# PEAK_LCW.net
KiCad netlist of a schematic drawn in Altium Designer
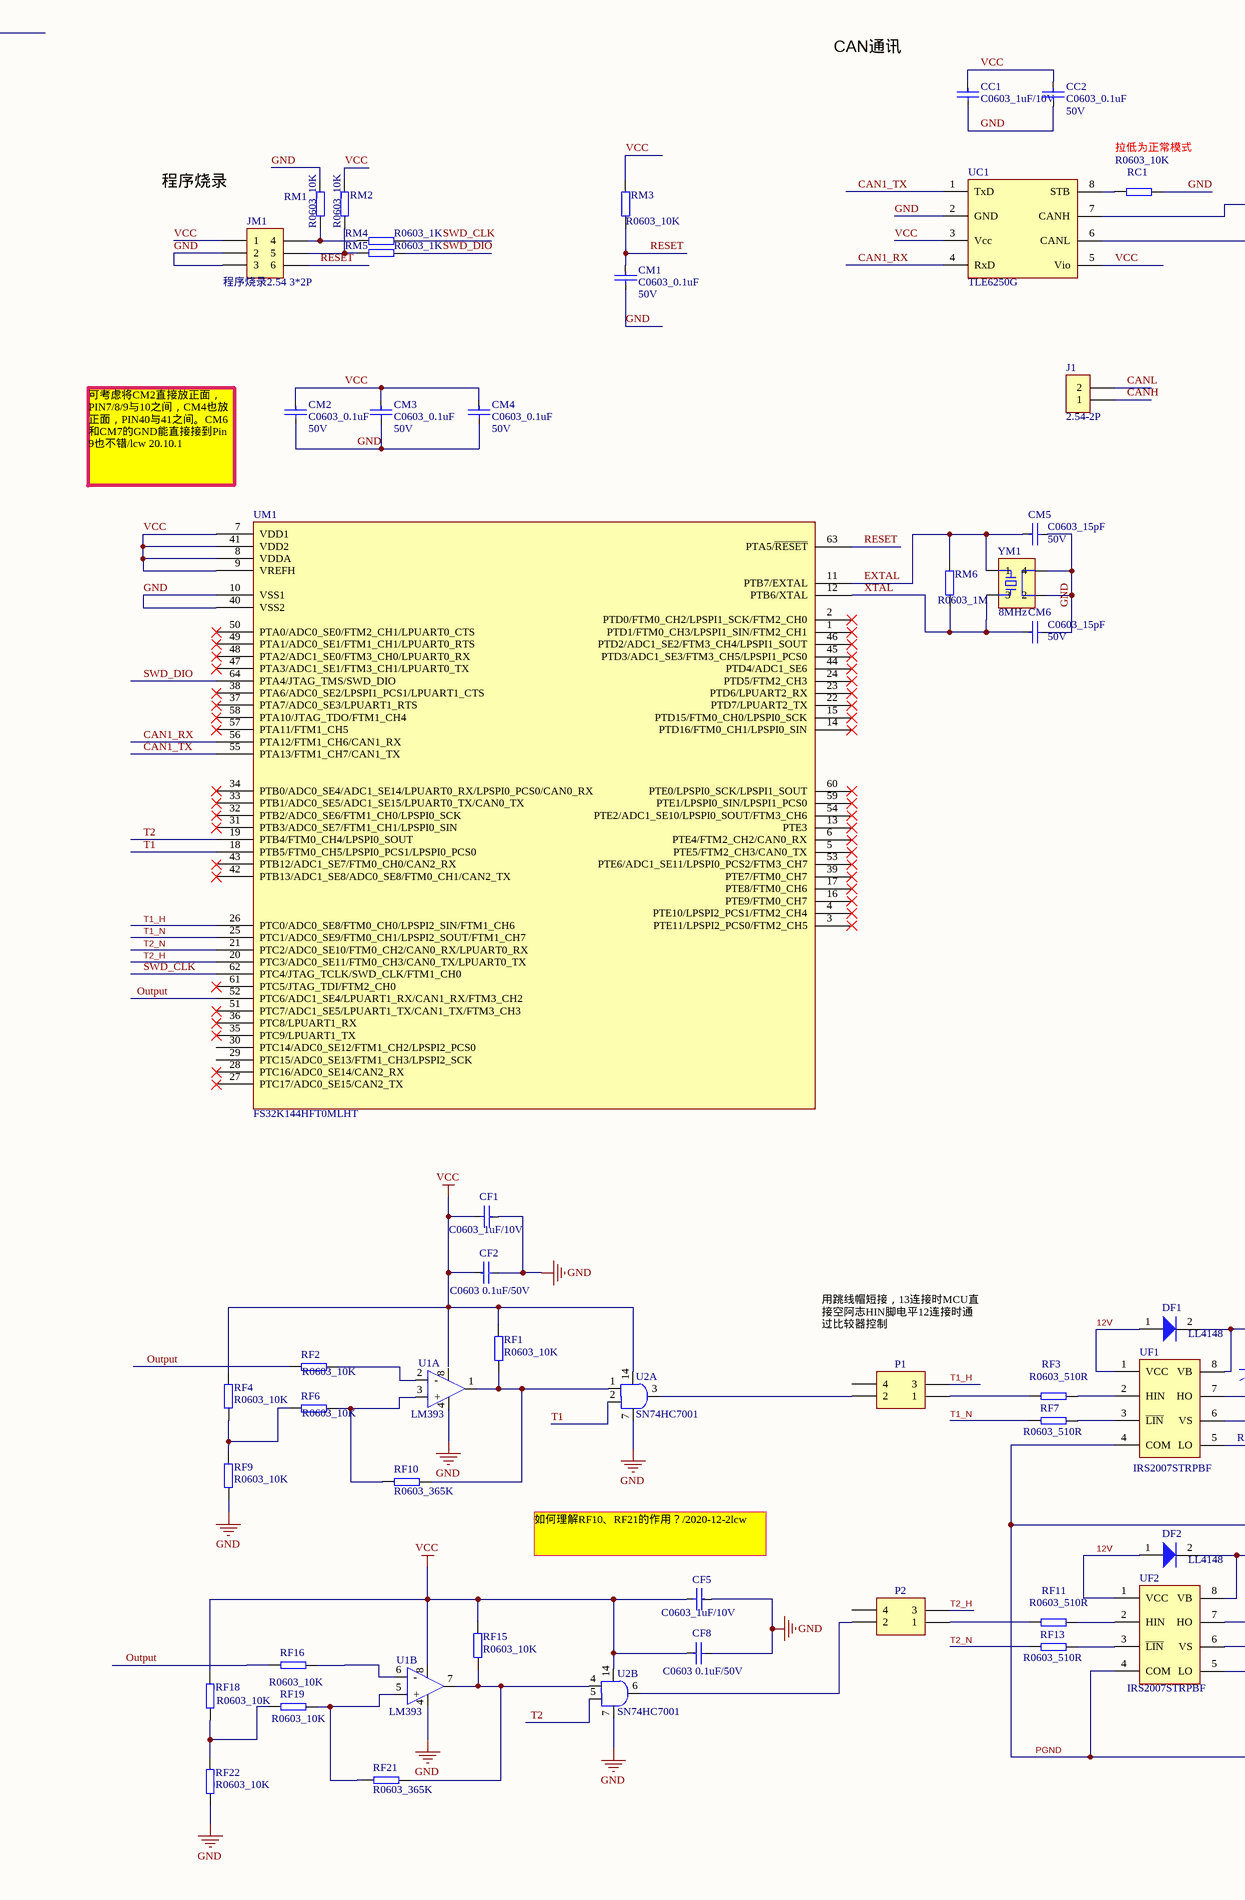
[diagram p0: PEAK——LCW.SchDoc, left]
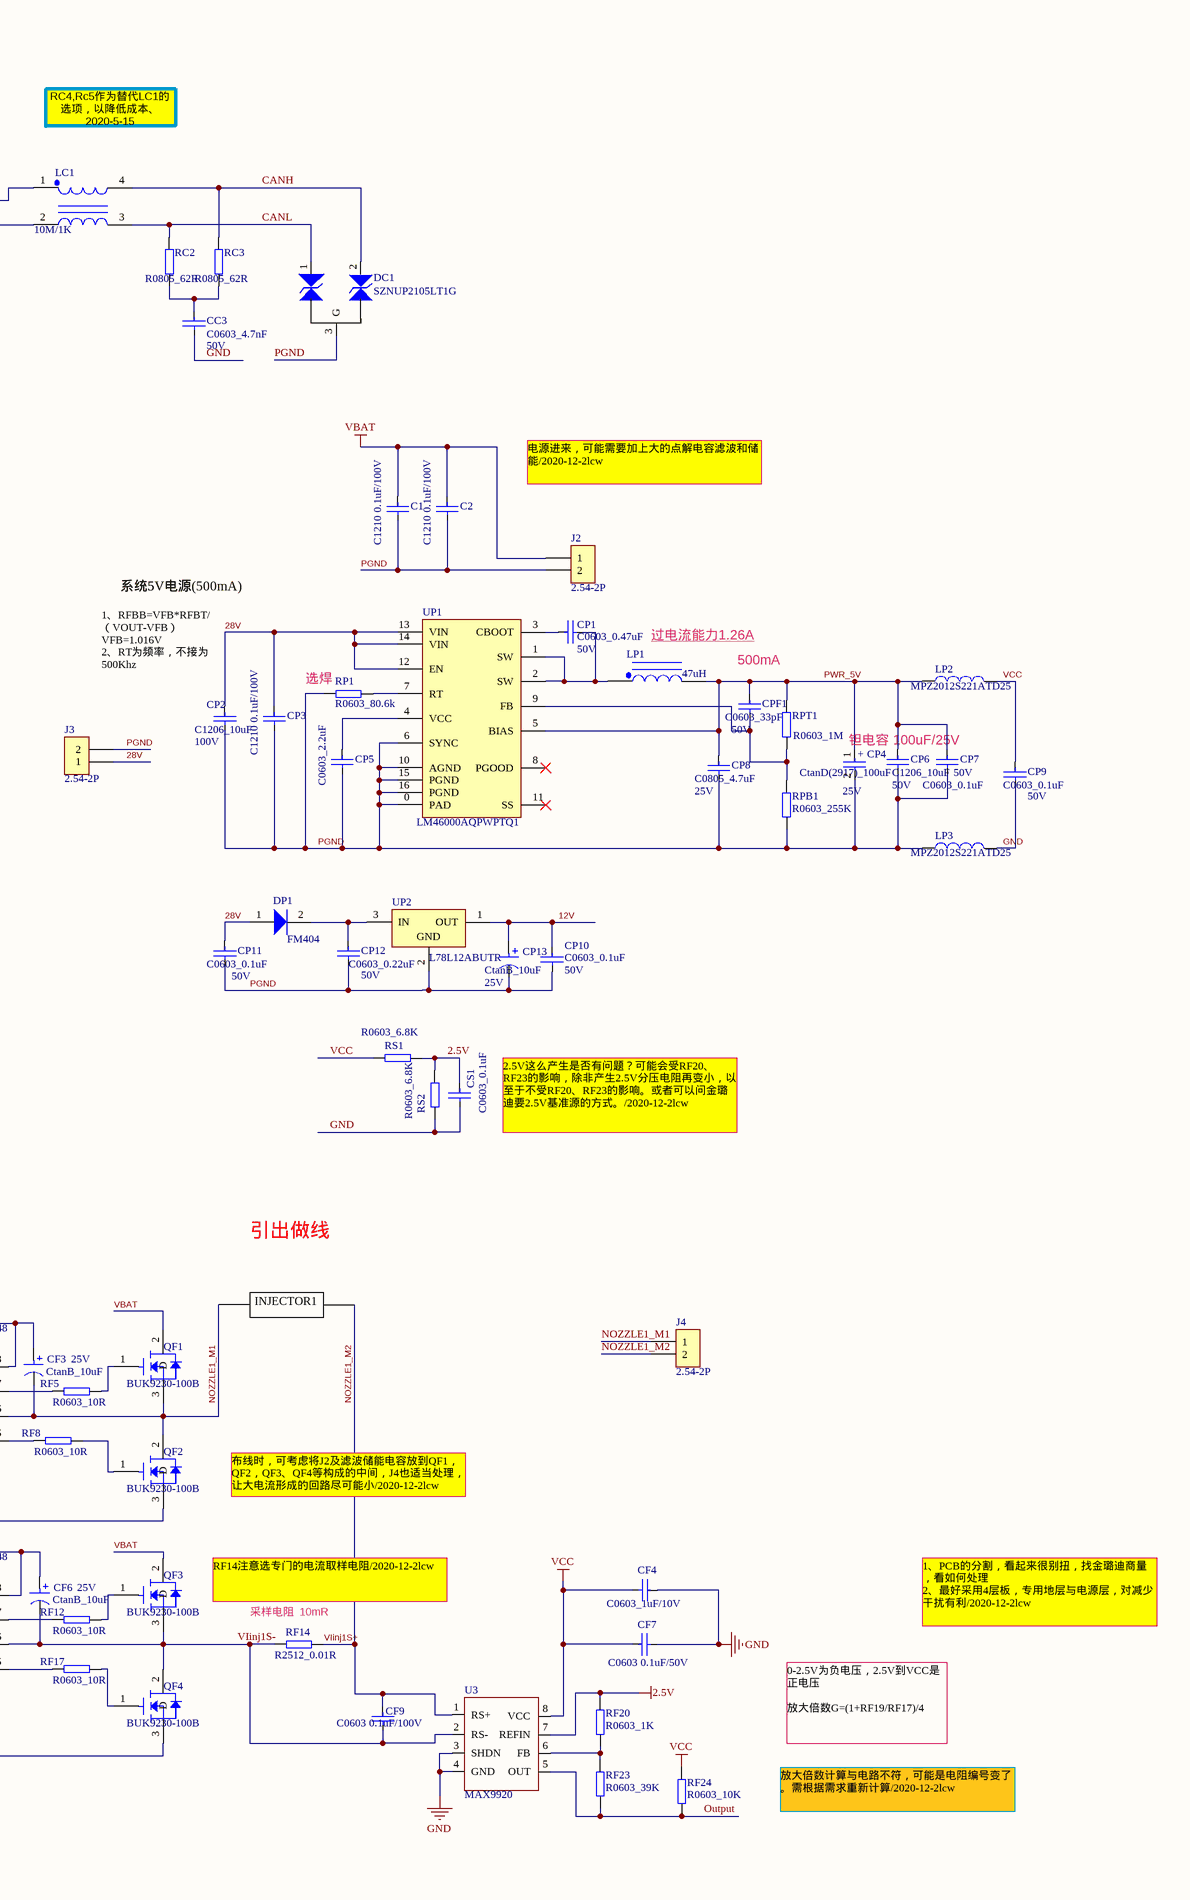
[diagram p1: PEAK——LCW.SchDoc, right]

(export (version "E")
  (design (tool "Eeschema 10.0.6"))
  (components
    (comp (ref "C1")
      (value "C1210 0.1uF/100V")
      (footprint "C1210")
      (description "C1210 0.1uF/50V 10%")
      (fields (field (name "VOLTAGE") "100V") (field (name "PART NUMBER") "3170014005"))
      (libsource (lib "BMSer") (part "CAP"))
    )
    (comp (ref "C2")
      (value "C1210 0.1uF/100V")
      (footprint "C1210")
      (description "C1210 0.1uF/50V 10%")
      (fields (field (name "VOLTAGE") "100V") (field (name "PART NUMBER") "3170014005"))
      (libsource (lib "BMSer") (part "CAP"))
    )
    (comp (ref "CC1")
      (value "C0603_1uF/10V")
      (footprint "C0603")
      (description "C0603 0.1uF/50V 10%")
      (fields (field (name "VOLTAGE") "10V") (field (name "PART NUMBER") "3170011015"))
      (libsource (lib "BMSer") (part "CAP"))
    )
    (comp (ref "CC2")
      (value "C0603_0.1uF")
      (footprint "C0603")
      (description "C0603 0.1uF/50V 10%")
      (fields
        (field (name "VOLTAGE") "50V")
        (field (name "PART NUMBER") "3170011015")
        (field (name "MANUFACTURER") "YAGEO")
      )
      (libsource (lib "BMSer") (part "CAP"))
    )
    (comp (ref "CC3")
      (value "C0603_4.7nF")
      (footprint "C0603")
      (description "C0603 4.7nF/50V 5% X7R")
      (fields
        (field (name "VOLTAGE") "50V")
        (field (name "PART NUMBER") "3170011009")
        (field (name "MANUFACTURER") "YAGEO")
      )
      (libsource (lib "BMSer") (part "CAP"))
    )
    (comp (ref "CF1")
      (value "C0603_1uF/10V")
      (footprint "C0603")
      (description "C0603 0.1uF/50V 10%")
      (fields (field (name "VOLTAGE") "10V") (field (name "PART NUMBER") "3170011015"))
      (libsource (lib "BMSer") (part "CAP"))
    )
    (comp (ref "CF2")
      (value "C0603 0.1uF/50V")
      (footprint "C0603")
      (description "C0603 0.1uF/50V 10%")
      (fields (field (name "VOLTAGE") "50V") (field (name "PART NUMBER") "3170011015"))
      (libsource (lib "BMSer") (part "CAP"))
    )
    (comp (ref "CF3")
      (value "CtanB_10uF")
      (footprint "CTANB")
      (description "CtanB(1210) 10uF/25V 10%")
      (fields
        (field (name "PART NUMBER") "3172690034")
        (field (name "MANUFACTURER") "AVX")
        (field (name "VOLTAGE") "25V")
      )
      (libsource (lib "BMSer") (part "CAP_T"))
    )
    (comp (ref "CF4")
      (value "C0603_1uF/10V")
      (footprint "C0603")
      (description "C0603 0.1uF/50V 10%")
      (fields (field (name "VOLTAGE") "10V") (field (name "PART NUMBER") "3170011015"))
      (libsource (lib "BMSer") (part "CAP"))
    )
    (comp (ref "CF5")
      (value "C0603_1uF/10V")
      (footprint "C0603")
      (description "C0603 0.1uF/50V 10%")
      (fields (field (name "VOLTAGE") "10V") (field (name "PART NUMBER") "3170011015"))
      (libsource (lib "BMSer") (part "CAP"))
    )
    (comp (ref "CF6")
      (value "CtanB_10uF")
      (footprint "CTANB")
      (description "CtanB(1210) 10uF/25V 10%")
      (fields
        (field (name "PART NUMBER") "3172690034")
        (field (name "MANUFACTURER") "AVX")
        (field (name "VOLTAGE") "25V")
      )
      (libsource (lib "BMSer") (part "CAP_T"))
    )
    (comp (ref "CF7")
      (value "C0603 0.1uF/50V")
      (footprint "C0603")
      (description "C0603 0.1uF/50V 10%")
      (fields (field (name "VOLTAGE") "50V") (field (name "PART NUMBER") "3170011015"))
      (libsource (lib "BMSer") (part "CAP"))
    )
    (comp (ref "CF8")
      (value "C0603 0.1uF/50V")
      (footprint "C0603")
      (description "C0603 0.1uF/50V 10%")
      (fields (field (name "VOLTAGE") "50V") (field (name "PART NUMBER") "3170011015"))
      (libsource (lib "BMSer") (part "CAP"))
    )
    (comp (ref "CF9")
      (value "C0603 0.1uF/100V")
      (footprint "C0603")
      (description "C0603 0.1uF/50V 10%")
      (fields (field (name "VOLTAGE") "50V") (field (name "PART NUMBER") "3170011015"))
      (libsource (lib "BMSer") (part "CAP"))
    )
    (comp (ref "CM1")
      (value "C0603_0.1uF")
      (footprint "C0603")
      (description "C0603 0.1uF/50V 10%")
      (fields
        (field (name "VOLTAGE") "50V")
        (field (name "PART NUMBER") "3170011015")
        (field (name "MANUFACTURER") "YAGEO")
      )
      (libsource (lib "BMSer") (part "CAP"))
    )
    (comp (ref "CM2")
      (value "C0603_0.1uF")
      (footprint "C0603")
      (description "C0603 0.1uF/50V 10%")
      (fields
        (field (name "VOLTAGE") "50V")
        (field (name "PART NUMBER") "3170011015")
        (field (name "MANUFACTURER") "YAGEO")
      )
      (libsource (lib "BMSer") (part "CAP"))
    )
    (comp (ref "CM3")
      (value "C0603_0.1uF")
      (footprint "C0603")
      (description "C0603 0.1uF/50V 10%")
      (fields
        (field (name "VOLTAGE") "50V")
        (field (name "PART NUMBER") "3170011015")
        (field (name "MANUFACTURER") "YAGEO")
      )
      (libsource (lib "BMSer") (part "CAP"))
    )
    (comp (ref "CM4")
      (value "C0603_0.1uF")
      (footprint "C0603")
      (description "C0603 0.1uF/50V 10%")
      (fields
        (field (name "VOLTAGE") "50V")
        (field (name "PART NUMBER") "3170011015")
        (field (name "MANUFACTURER") "YAGEO")
      )
      (libsource (lib "BMSer") (part "CAP"))
    )
    (comp (ref "CM5")
      (value "C0603_15pF")
      (footprint "C0603")
      (description "C0603 15pF/50V 10%")
      (fields
        (field (name "VOLTAGE") "50V")
        (field (name "PART NUMBER") "3172510040")
        (field (name "MANUFACTURER") "YAGEO")
      )
      (libsource (lib "BMSer") (part "CAP"))
    )
    (comp (ref "CM6")
      (value "C0603_15pF")
      (footprint "C0603")
      (description "C0603 15pF/50V 10%")
      (fields
        (field (name "VOLTAGE") "50V")
        (field (name "PART NUMBER") "3172510040")
        (field (name "MANUFACTURER") "YAGEO")
      )
      (libsource (lib "BMSer") (part "CAP"))
    )
    (comp (ref "CP1")
      (value "C0603_0.47uF")
      (footprint "C0603")
      (description "C0603 0.47uF/50V 10%")
      (fields
        (field (name "VOLTAGE") "50V")
        (field (name "PART NUMBER") "3170011017")
        (field (name "MANUFACTURER") "murata")
      )
      (libsource (lib "BMSer") (part "CAP"))
    )
    (comp (ref "CP2")
      (value "C1206_10uF")
      (footprint "C1206")
      (description "C1206 10uF/50V  10%")
      (fields
        (field (name "VOLTAGE") "100V")
        (field (name "PART NUMBER") "3172530019")
        (field (name "MANUFACTURER") "YAGEO")
      )
      (libsource (lib "BMSer") (part "CAP"))
    )
    (comp (ref "CP3")
      (value "C1210 0.1uF/100V")
      (footprint "C1210")
      (description "C1210 0.1uF/100V 10%")
      (fields (field (name "VOLTAGE") "100V") (field (name "PART NUMBER") "3170014005"))
      (libsource (lib "BMSer") (part "CAP"))
    )
    (comp (ref "CP4")
      (value "CtanD(2917)_100uF")
      (footprint "CTAND")
      (description "CtanD(2917) 100uF/25V 10%")
      (fields
        (field (name "VOLTAGE") "25V")
        (field (name "PART NUMBER") "3170030004")
        (field (name "MANUFACTURER") "AVX")
      )
      (libsource (lib "BMSer") (part "CAP_E"))
    )
    (comp (ref "CP5")
      (value "C0603_2.2uF")
      (footprint "C0603")
      (description "C0603 2.2uF/50V 10%")
      (fields (field (name "VOLTAGE") "50V") (field (name "PART NUMBER") "3170011030"))
      (libsource (lib "BMSer") (part "CAP"))
    )
    (comp (ref "CP6")
      (value "C1206_10uF")
      (footprint "C1206")
      (description "C1206 10uF/50V  10%")
      (fields
        (field (name "VOLTAGE") "50V")
        (field (name "PART NUMBER") "3172530019")
        (field (name "MANUFACTURER") "YAGEO")
      )
      (libsource (lib "BMSer") (part "CAP"))
    )
    (comp (ref "CP7")
      (value "C0603_0.1uF")
      (footprint "C0603")
      (description "C0603 0.1uF/50V 10%")
      (fields
        (field (name "VOLTAGE") "50V")
        (field (name "PART NUMBER") "3170011015")
        (field (name "MANUFACTURER") "YAGEO")
      )
      (libsource (lib "BMSer") (part "CAP"))
    )
    (comp (ref "CP8")
      (value "C0805_4.7uF")
      (footprint "C0805")
      (description "C0805 4.7uF/25V 10%")
      (fields
        (field (name "VOLTAGE") "25V")
        (field (name "PART NUMBER") "3170012010")
        (field (name "MANUFACTURER") "YAGEO")
      )
      (libsource (lib "BMSer") (part "CAP"))
    )
    (comp (ref "CP9")
      (value "C0603_0.1uF")
      (footprint "C0603")
      (description "C0603 0.1uF/50V 10%")
      (fields
        (field (name "VOLTAGE") "50V")
        (field (name "PART NUMBER") "3170011015")
        (field (name "MANUFACTURER") "YAGEO")
      )
      (libsource (lib "BMSer") (part "CAP"))
    )
    (comp (ref "CP10")
      (value "C0603_0.1uF")
      (footprint "C0603")
      (description "C0603 0.1uF/50V 10%  X7R")
      (fields
        (field (name "VOLTAGE") "50V")
        (field (name "PART NUMBER") "3170011015")
        (field (name "MANUFACTURER") "YAGEO")
      )
      (libsource (lib "BMSer") (part "CAP"))
    )
    (comp (ref "CP11")
      (value "C0603_0.1uF")
      (footprint "C0603")
      (description "C0603 0.1uF/50V 10%")
      (fields
        (field (name "VOLTAGE") "50V")
        (field (name "PART NUMBER") "3170011015")
        (field (name "MANUFACTURER") "YAGEO")
      )
      (libsource (lib "BMSer") (part "CAP"))
    )
    (comp (ref "CP12")
      (value "C0603_0.22uF")
      (footprint "C0603")
      (description "C0603 0.22uF/50V 10%")
      (fields
        (field (name "VOLTAGE") "50V")
        (field (name "PART NUMBER") "3172510028")
        (field (name "MANUFACTURER") "YAGEO")
      )
      (libsource (lib "BMSer") (part "CAP"))
    )
    (comp (ref "CP13")
      (value "CtanB_10uF")
      (footprint "CTANB")
      (description "CtanB(1210) 10uF/25V 10%")
      (fields
        (field (name "PART NUMBER") "3172690034")
        (field (name "MANUFACTURER") "AVX")
        (field (name "VOLTAGE") "25V")
      )
      (libsource (lib "BMSer") (part "CAP_T"))
    )
    (comp (ref "CPF1")
      (value "C0603_33pF")
      (footprint "C0603")
      (description "C0603 33pF/50V 10%")
      (fields
        (field (name "VOLTAGE") "50V")
        (field (name "PART NUMBER") "3172510041")
        (field (name "MANUFACTURER") "YAGEO")
      )
      (libsource (lib "BMSer") (part "CAP"))
    )
    (comp (ref "CS1")
      (value "C0603_0.1uF")
      (footprint "C0603")
      (description "C0603 0.1uF/50V 10%")
      (fields (field (name "VOLTAGE") "50V") (field (name "PART NUMBER") "3170011015"))
      (libsource (lib "BMSer") (part "CAP"))
    )
    (comp (ref "DC1")
      (value "SZNUP2105LT1G")
      (footprint "SOT-23")
      (description "SOT-23 SZNUP2105LT1G")
      (fields (field (name "PART NUMBER") "3110050073") (field (name "MANUFACTURER") "ON"))
      (libsource (lib "BMSer") (part "SZNUP2105LT1G"))
    )
    (comp (ref "DF1")
      (value "LL4148")
      (footprint "SOD-80")
      (description "SOD-80  LL4148 2A/75V")
      (fields (field (name "PART NUMBER") "3110010015") (field (name "MANUFACTURER") "VISHA"))
      (libsource (lib "BMSer") (part "DIODE"))
    )
    (comp (ref "DF2")
      (value "LL4148")
      (footprint "SOD-80")
      (description "SOD-80  LL4148 2A/75V")
      (fields (field (name "PART NUMBER") "3110010015") (field (name "MANUFACTURER") "VISHA"))
      (libsource (lib "BMSer") (part "DIODE"))
    )
    (comp (ref "DP1")
      (value "FM404")
      (footprint "D0-214AC")
      (description "D0-214AC FM404")
      (fields (field (name "PART NUMBER") "13110010013") (field (name "MANUFACTURER") "LRC"))
      (libsource (lib "BMSer") (part "DIODE"))
    )
    (comp (ref "J1")
      (value "2.54-2P")
      (footprint "2.54-2P")
      (fields (field (name "PART NUMBER") "53190010200"))
      (libsource (lib "") (part "CON2_1"))
    )
    (comp (ref "J2")
      (value "2.54-2P")
      (footprint "2.54-2P")
      (fields (field (name "PART NUMBER") "53190010200"))
      (libsource (lib "BMSer") (part "CON2"))
    )
    (comp (ref "J3")
      (value "2.54-2P")
      (footprint "2.54-2P")
      (fields (field (name "PART NUMBER") "53190010200"))
      (libsource (lib "") (part "CON2_1"))
    )
    (comp (ref "J4")
      (value "2.54-2P")
      (footprint "2.54-2P")
      (fields (field (name "PART NUMBER") "53190010200"))
      (libsource (lib "BMSer") (part "CON2"))
    )
    (comp (ref "JM1")
      (value "程序烧录2.54 3*2P")
      (footprint "3x2P")
      (fields (field (name "PART NUMBER") "53190010221"))
      (libsource (lib "BMSer") (part "CON3x2"))
    )
    (comp (ref "LC1")
      (value "10M/1K")
      (footprint "ACT45B")
      (description "ACT45B-510-2P-TL  10M/1K/0.2A")
      (fields (field (name "PART NUMBER") "3180020022") (field (name "MANUFACTURER") "TDK"))
      (libsource (lib "BMSer") (part "INDUCTOR3"))
    )
    (comp (ref "LP1")
      (value "47uH")
      (footprint "LGK")
      (description "CLF7045NIT-470M-D  47uH/1.26A  Q")
      (fields (field (name "PART NUMBER") "53180020033") (field (name "MANUFACTURER") "TDK"))
      (libsource (lib "BMSer") (part "INDUCTOR2"))
    )
    (comp (ref "LP2")
      (value "MPZ2012S221ATD25")
      (footprint "L 0805")
      (description "L0805 MPZ2012S221ATD25")
      (fields (field (name "PART NUMBER") "53180020011") (field (name "MANUFACTURER") "TDK"))
      (libsource (lib "BMSer") (part "INDUCTOR1"))
    )
    (comp (ref "LP3")
      (value "MPZ2012S221ATD25")
      (footprint "L 0805")
      (description "L0805 MPZ2012S221ATD25")
      (fields (field (name "PART NUMBER") "53180020011") (field (name "MANUFACTURER") "TDK"))
      (libsource (lib "BMSer") (part "INDUCTOR1"))
    )
    (comp (ref "P1")
      (value "Header 2X2")
      (footprint "HDR2X2")
      (description "Header, 2-Pin, Dual row")
      (fields (field (name "PUBLISHER") "Altium Limited"))
      (libsource (lib "Miscellaneous Connectors") (part "Header 2X2"))
    )
    (comp (ref "P2")
      (value "Header 2X2")
      (footprint "HDR2X2")
      (description "Header, 2-Pin, Dual row")
      (fields (field (name "PUBLISHER") "Altium Limited"))
      (libsource (lib "Miscellaneous Connectors") (part "Header 2X2"))
    )
    (comp (ref "QF1")
      (value "BUK9230-100B")
      (footprint "DPAK-3_L6.6-W6.1-P2.28-LS9.9-BR")
      (description "TO-252-3 FDD86567-F085 60V/100A")
      (fields (field (name "PART NUMBER") "53110022012") (field (name "MANUFACTURER") "ON"))
      (libsource (lib "BMSer") (part "NMOSGDS"))
    )
    (comp (ref "QF2")
      (value "BUK9230-100B")
      (footprint "DPAK-3_L6.6-W6.1-P2.28-LS9.9-BR")
      (description "TO-252-3 FDD86567-F085 60V/100A")
      (fields (field (name "PART NUMBER") "53110022012") (field (name "MANUFACTURER") "ON"))
      (libsource (lib "BMSer") (part "NMOSGDS"))
    )
    (comp (ref "QF3")
      (value "BUK9230-100B")
      (footprint "DPAK-3_L6.6-W6.1-P2.28-LS9.9-BR")
      (description "TO-252-3 FDD86567-F085 60V/100A")
      (fields (field (name "PART NUMBER") "53110022012") (field (name "MANUFACTURER") "ON"))
      (libsource (lib "BMSer") (part "NMOSGDS"))
    )
    (comp (ref "QF4")
      (value "BUK9230-100B")
      (footprint "DPAK-3_L6.6-W6.1-P2.28-LS9.9-BR")
      (description "TO-252-3 FDD86567-F085 60V/100A")
      (fields (field (name "PART NUMBER") "53110022012") (field (name "MANUFACTURER") "ON"))
      (libsource (lib "BMSer") (part "NMOSGDS"))
    )
    (comp (ref "RC1")
      (value "R0603_10K")
      (footprint "R0603")
      (description "R0603 1/10w 10K 1%")
      (fields (field (name "PART NUMBER") "3160030053") (field (name "MANUFACTURER") "YAGEO"))
      (libsource (lib "BMSer") (part "RS"))
    )
    (comp (ref "RC2")
      (value "R0805_62R")
      (footprint "R0805")
      (description "R0805 1/8w10R 1%")
      (fields (field (name "PART NUMBER") "3160050016") (field (name "MANUFACTURER") "YAGEO"))
      (libsource (lib "BMSer") (part "RS"))
    )
    (comp (ref "RC3")
      (value "R0805_62R")
      (footprint "R0805")
      (description "R0805 1/8w10R 1%")
      (fields (field (name "PART NUMBER") "3160050016") (field (name "MANUFACTURER") "YAGEO"))
      (libsource (lib "BMSer") (part "RS"))
    )
    (comp (ref "RF1")
      (value "R0603_10K")
      (footprint "R0603")
      (description "R0603 1/10w 10K 1%")
      (fields (field (name "PART NUMBER") "3160030053") (field (name "MANUFACTURER") "YAGEO"))
      (libsource (lib "BMSer") (part "RS"))
    )
    (comp (ref "RF2")
      (value "R0603_10K")
      (footprint "R0603")
      (description "R0603 1/10w 10K 1%")
      (fields (field (name "PART NUMBER") "3160030053") (field (name "MANUFACTURER") "YAGEO"))
      (libsource (lib "BMSer") (part "RS"))
    )
    (comp (ref "RF3")
      (value "R0603_510R")
      (footprint "R0603")
      (description "R0603  1/10w 510R 1%")
      (fields (field (name "PART NUMBER") "3160030020") (field (name "MANUFACTURER") "YAGEO"))
      (libsource (lib "BMSer") (part "RS"))
    )
    (comp (ref "RF4")
      (value "R0603_10K")
      (footprint "R0603")
      (description "R0603 1/10w 10K 1%")
      (fields (field (name "PART NUMBER") "3160030053") (field (name "MANUFACTURER") "YAGEO"))
      (libsource (lib "BMSer") (part "RS"))
    )
    (comp (ref "RF5")
      (value "R0603_10R")
      (footprint "R0603")
      (description "R0603 1/10w  10R 1%")
      (fields (field (name "PART NUMBER") "3160030193") (field (name "MANUFACTURER") "YAGEO"))
      (libsource (lib "BMSer") (part "RS"))
    )
    (comp (ref "RF6")
      (value "R0603_10K")
      (footprint "R0603")
      (description "R0603 1/10w 10K 1%")
      (fields (field (name "PART NUMBER") "3160030053") (field (name "MANUFACTURER") "YAGEO"))
      (libsource (lib "BMSer") (part "RS"))
    )
    (comp (ref "RF7")
      (value "R0603_510R")
      (footprint "R0603")
      (description "R0603  1/10w 510R 1%")
      (fields (field (name "PART NUMBER") "3160030020") (field (name "MANUFACTURER") "YAGEO"))
      (libsource (lib "BMSer") (part "RS"))
    )
    (comp (ref "RF8")
      (value "R0603_10R")
      (footprint "R0603")
      (description "R0603 1/10w  10R 1%")
      (fields (field (name "PART NUMBER") "3160030193") (field (name "MANUFACTURER") "YAGEO"))
      (libsource (lib "BMSer") (part "RS"))
    )
    (comp (ref "RF9")
      (value "R0603_10K")
      (footprint "R0603")
      (description "R0603 1/10w 10K 1%")
      (fields (field (name "PART NUMBER") "3160030053") (field (name "MANUFACTURER") "YAGEO"))
      (libsource (lib "BMSer") (part "RS"))
    )
    (comp (ref "RF10")
      (value "R0603_365K")
      (footprint "R0603")
      (description "R0603 1/10w 365K 1%")
      (fields (field (name "PART NUMBER") "3160030166") (field (name "MANUFACTURER") "YAGEO"))
      (libsource (lib "BMSer") (part "RS"))
    )
    (comp (ref "RF11")
      (value "R0603_510R")
      (footprint "R0603")
      (description "R0603  1/10w 510R 1%")
      (fields (field (name "PART NUMBER") "3160030020") (field (name "MANUFACTURER") "YAGEO"))
      (libsource (lib "BMSer") (part "RS"))
    )
    (comp (ref "RF12")
      (value "R0603_10R")
      (footprint "R0603")
      (description "R0603 1/10w  10R 1%")
      (fields (field (name "PART NUMBER") "3160030193") (field (name "MANUFACTURER") "YAGEO"))
      (libsource (lib "BMSer") (part "RS"))
    )
    (comp (ref "RF13")
      (value "R0603_510R")
      (footprint "R0603")
      (description "R0603  1/10w 510R 1%")
      (fields (field (name "PART NUMBER") "3160030020") (field (name "MANUFACTURER") "YAGEO"))
      (libsource (lib "BMSer") (part "RS"))
    )
    (comp (ref "RF14")
      (value "R2512_0.01R")
      (footprint "R2512")
      (description "R2512 1W 0.01R 1%")
      (fields (field (name "PART NUMBER") "3162380033") (field (name "MANUFACTURER") "YAGEO"))
      (libsource (lib "BMSer") (part "RS"))
    )
    (comp (ref "RF15")
      (value "R0603_10K")
      (footprint "R0603")
      (description "R0603 1/10w 10K 1%")
      (fields (field (name "PART NUMBER") "3160030053") (field (name "MANUFACTURER") "YAGEO"))
      (libsource (lib "BMSer") (part "RS"))
    )
    (comp (ref "RF16")
      (value "R0603_10K")
      (footprint "R0603")
      (description "R0603 1/10w 10K 1%")
      (fields (field (name "PART NUMBER") "3160030053") (field (name "MANUFACTURER") "YAGEO"))
      (libsource (lib "BMSer") (part "RS"))
    )
    (comp (ref "RF17")
      (value "R0603_10R")
      (footprint "R0603")
      (description "R0603 1/10w  10R 1%")
      (fields (field (name "PART NUMBER") "3160030193") (field (name "MANUFACTURER") "YAGEO"))
      (libsource (lib "BMSer") (part "RS"))
    )
    (comp (ref "RF18")
      (value "R0603_10K")
      (footprint "R0603")
      (description "R0603 1/10w 10K 1%")
      (fields (field (name "PART NUMBER") "3160030053") (field (name "MANUFACTURER") "YAGEO"))
      (libsource (lib "BMSer") (part "RS"))
    )
    (comp (ref "RF19")
      (value "R0603_10K")
      (footprint "R0603")
      (description "R0603 1/10w 10K 1%")
      (fields (field (name "PART NUMBER") "3160030053") (field (name "MANUFACTURER") "YAGEO"))
      (libsource (lib "BMSer") (part "RS"))
    )
    (comp (ref "RF20")
      (value "R0603_1K")
      (footprint "R0603")
      (description "R0603  1/10w 1K 1%")
      (fields (field (name "PART NUMBER") "3160030021") (field (name "MANUFACTURER") "YAGEO"))
      (libsource (lib "BMSer") (part "RS"))
    )
    (comp (ref "RF21")
      (value "R0603_365K")
      (footprint "R0603")
      (description "R0603 1/10w 365K 1%")
      (fields (field (name "PART NUMBER") "3160030166") (field (name "MANUFACTURER") "YAGEO"))
      (libsource (lib "BMSer") (part "RS"))
    )
    (comp (ref "RF22")
      (value "R0603_10K")
      (footprint "R0603")
      (description "R0603 1/10w 10K 1%")
      (fields (field (name "PART NUMBER") "3160030053") (field (name "MANUFACTURER") "YAGEO"))
      (libsource (lib "BMSer") (part "RS"))
    )
    (comp (ref "RF23")
      (value "R0603_39K")
      (footprint "R0603")
      (description "R0603 1/10w 39K 1%")
      (fields (field (name "PART NUMBER") "3160030165") (field (name "MANUFACTURER") "YAGEO/UNIOHM"))
      (libsource (lib "BMSer") (part "RS"))
    )
    (comp (ref "RF24")
      (value "R0603_10K")
      (footprint "R0603")
      (description "R0603 1/10w 10K 1%")
      (fields (field (name "PART NUMBER") "3160030053") (field (name "MANUFACTURER") "YAGEO"))
      (libsource (lib "BMSer") (part "RS"))
    )
    (comp (ref "RM1")
      (value "R0603_10K")
      (footprint "R0603")
      (description "R0603 1/10w 10K 1%")
      (fields (field (name "PART NUMBER") "3160030053") (field (name "MANUFACTURER") "YAGEO"))
      (libsource (lib "BMSer") (part "RS"))
    )
    (comp (ref "RM2")
      (value "R0603_10K")
      (footprint "R0603")
      (description "R0603 1/10w 10K 1%")
      (fields (field (name "PART NUMBER") "3160030053") (field (name "MANUFACTURER") "YAGEO"))
      (libsource (lib "BMSer") (part "RS"))
    )
    (comp (ref "RM3")
      (value "R0603_10K")
      (footprint "R0603")
      (description "R0603 1/10w 10K 1%")
      (fields (field (name "PART NUMBER") "3160030053") (field (name "MANUFACTURER") "YAGEO"))
      (libsource (lib "BMSer") (part "RS"))
    )
    (comp (ref "RM4")
      (value "R0603_1K")
      (footprint "R0603")
      (description "R0603  1/10w 1K 1%")
      (fields (field (name "PART NUMBER") "3160030021") (field (name "MANUFACTURER") "YAGEO"))
      (libsource (lib "BMSer") (part "RS"))
    )
    (comp (ref "RM5")
      (value "R0603_1K")
      (footprint "R0603")
      (description "R0603  1/10w 1K 1%")
      (fields (field (name "PART NUMBER") "3160030021") (field (name "MANUFACTURER") "YAGEO"))
      (libsource (lib "BMSer") (part "RS"))
    )
    (comp (ref "RM6")
      (value "R0603_1M")
      (footprint "R0603")
      (description "R0603 1/10w 1M 1%")
      (fields (field (name "PART NUMBER") "3160030183") (field (name "MANUFACTURER") "YAGEO/UNIOHM"))
      (libsource (lib "BMSer") (part "RS"))
    )
    (comp (ref "RP1")
      (value "R0603_80.6k")
      (footprint "R0603")
      (description "R0603 1/10w 80.6k 1%")
      (fields (field (name "PART NUMBER") "3162310230") (field (name "MANUFACTURER") "YAGEO"))
      (libsource (lib "BMSer") (part "RS"))
    )
    (comp (ref "RPB1")
      (value "R0603_255K")
      (footprint "R0603")
      (description "R0603 1/10w255K 1%")
      (fields (field (name "PART NUMBER") "3160030153") (field (name "MANUFACTURER") "YAGEO"))
      (libsource (lib "BMSer") (part "RS"))
    )
    (comp (ref "RPT1")
      (value "R0603_1M")
      (footprint "R0603")
      (description "R0603 1/10w 1M 1%")
      (fields (field (name "PART NUMBER") "3160030183") (field (name "MANUFACTURER") "YAGEO/UNIOHM"))
      (libsource (lib "BMSer") (part "RS"))
    )
    (comp (ref "RS1")
      (value "R0603_6.8K")
      (footprint "R0603")
      (description "R0603 1/10w 6.8K")
      (fields (field (name "PART NUMBER") "3160030047") (field (name "MANUFACTURER") "YAGEO"))
      (libsource (lib "BMSer") (part "RS"))
    )
    (comp (ref "RS2")
      (value "R0603_6.8K")
      (footprint "R0603")
      (description "R0603  1/10w 2.4K")
      (fields (field (name "PART NUMBER") "3160030031") (field (name "MANUFACTURER") "YAGEO"))
      (libsource (lib "BMSer") (part "RS"))
    )
    (comp (ref "U1")
      (value "LM393")
      (footprint "SOIC-8_L5.0-W4.0-P1.27-LS6.0-BL")
      (libsource (lib "Schlib1") (part "LM393"))
    )
    (comp (ref "U2")
      (value "SN74HC7001")
      (footprint "SOIC-14_L8.7-W3.9-P1.27-LS6.0-BL")
      (libsource (lib "Schlib1") (part "SN74HC7001"))
    )
    (comp (ref "U3")
      (value "MAX9920")
      (footprint "SOIC-8_L5.0-W4.0-P1.27-LS6.0-BL")
      (libsource (lib "Schlib1") (part "MAX9920"))
    )
    (comp (ref "UC1")
      (value "TLE6250G")
      (footprint "PG-DSO-8")
      (description "PG-DSO-8 TLE9251VSJ")
      (fields (field (name "PART NUMBER") "3100050124") (field (name "MANUFACTURER") "infineon"))
      (libsource (lib "BMSer") (part "TLE9251VSJ"))
    )
    (comp (ref "UF1")
      (value "IRS2007STRPBF")
      (footprint "SOIC-8L")
      (description "SOIC-8L IRS2007STRPBF")
      (fields (field (name "PART NUMBER") "3100050121") (field (name "MANUFACTURER") "infineon"))
      (libsource (lib "BMSer") (part "IRS2007STRPBF"))
    )
    (comp (ref "UF2")
      (value "IRS2007STRPBF")
      (footprint "SOIC-8L")
      (description "SOIC-8L IRS2007STRPBF")
      (fields (field (name "PART NUMBER") "3100050121") (field (name "MANUFACTURER") "infineon"))
      (libsource (lib "BMSer") (part "IRS2007STRPBF"))
    )
    (comp (ref "UM1")
      (value "FS32K144HFT0MLHT")
      (footprint "LQFP-64")
      (description "LQFP-64 FS32K144HFT0MLHT")
      (fields (field (name "PART NUMBER") "3100010021") (field (name "MANUFACTURER") "NXP"))
      (libsource (lib "BMSer") (part "FS32K144HFT0MLHT"))
    )
    (comp (ref "UP1")
      (value "LM46000AQPWPTQ1")
      (footprint "HTSSOP-16")
      (description "HTSSOP-16 LM46000AQPWPTQ1 60V/0.5A降压  Q")
      (fields (field (name "PART NUMBER") "3100050127") (field (name "MANUFACTURER") "TI"))
      (libsource (lib "BMSer") (part "LM46000AQPWPTQ1"))
    )
    (comp (ref "UP2")
      (value "L78L12ABUTR")
      (footprint "SOT-89")
      (description "SOT-89 L78L12ABUTR")
      (fields (field (name "PART NUMBER") "3100050105") (field (name "MANUFACTURER") "ST"))
      (libsource (lib "BMSer") (part "L78L12ABUTR"))
    )
    (comp (ref "YM1")
      (value "8MHz")
      (footprint "5.0*3.2_4")
      (description "5.0*3.2  8MHz 15pF")
      (fields (field (name "PART NUMBER") "53120010026") (field (name "MANUFACTURER") "HKC"))
      (libsource (lib "BMSer") (part "XTAL_4"))
    )
  )
  (nets
    (net (code "1") (name "/12V") (class "Default")
      (node (ref "CP10") (pin "1") (pintype "passive"))
      (node (ref "CP13") (pin "1") (pinfunction "1_1") (pintype "passive"))
      (node (ref "DF1") (pin "1") (pinfunction "1_1") (pintype "passive"))
      (node (ref "DF2") (pin "1") (pinfunction "1_1") (pintype "passive"))
      (node (ref "UF1") (pin "1") (pinfunction "VCC_1") (pintype "passive"))
      (node (ref "UF2") (pin "1") (pinfunction "VCC_1") (pintype "passive"))
      (node (ref "UP2") (pin "1") (pinfunction "OUT_1") (pintype "passive"))
    )
    (net (code "2") (name "/28V") (class "Default")
      (node (ref "CP11") (pin "1") (pintype "passive"))
      (node (ref "CP2") (pin "1") (pintype "passive"))
      (node (ref "CP3") (pin "1") (pintype "passive"))
      (node (ref "DP1") (pin "1") (pinfunction "1_1") (pintype "passive"))
      (node (ref "J3") (pin "1") (pinfunction "1_1") (pintype "passive"))
      (node (ref "UP1") (pin "12") (pinfunction "EN_12") (pintype "passive"))
      (node (ref "UP1") (pin "13") (pinfunction "VIN_13") (pintype "passive"))
      (node (ref "UP1") (pin "14") (pinfunction "VIN_14") (pintype "passive"))
    )
    (net (code "3") (name "/CAN1_RX") (class "Default")
      (node (ref "UC1") (pin "4") (pinfunction "RxD_4") (pintype "passive"))
      (node (ref "UM1") (pin "56") (pinfunction "PTA12/FTM1_CH6/CAN1_RX_56") (pintype "passive"))
    )
    (net (code "4") (name "/CAN1_TX") (class "Default")
      (node (ref "UC1") (pin "1") (pinfunction "TxD_1") (pintype "passive"))
      (node (ref "UM1") (pin "55") (pinfunction "PTA13/FTM1_CH7/CAN1_TX_55") (pintype "passive"))
    )
    (net (code "5") (name "/CANH") (class "Default")
      (node (ref "DC1") (pin "2") (pinfunction "2_2") (pintype "passive"))
      (node (ref "J1") (pin "1") (pinfunction "1_1") (pintype "passive"))
      (node (ref "LC1") (pin "4") (pinfunction "4_4") (pintype "passive"))
      (node (ref "RC3") (pin "2") (pintype "passive"))
    )
    (net (code "6") (name "/CANL") (class "Default")
      (node (ref "DC1") (pin "1") (pinfunction "1_1") (pintype "passive"))
      (node (ref "J1") (pin "2") (pinfunction "2_2") (pintype "passive"))
      (node (ref "LC1") (pin "3") (pinfunction "3_3") (pintype "passive"))
      (node (ref "RC2") (pin "2") (pintype "passive"))
    )
    (net (code "7") (name "/EXTAL") (class "Default")
      (node (ref "CM5") (pin "1") (pintype "passive"))
      (node (ref "RM6") (pin "2") (pintype "passive"))
      (node (ref "UM1") (pin "11") (pinfunction "PTB7/EXTAL_11") (pintype "passive"))
      (node (ref "YM1") (pin "1") (pinfunction "1_1") (pintype "passive"))
    )
    (net (code "8") (name "/NOZZLE1_M1") (class "Default")
      (node (ref "CF3") (pin "2") (pinfunction "2_2") (pintype "passive"))
      (node (ref "J4") (pin "1") (pinfunction "1_1") (pintype "passive"))
      (node (ref "QF1") (pin "3") (pinfunction "S_3") (pintype "passive"))
      (node (ref "QF2") (pin "2") (pinfunction "D_2") (pintype "passive"))
      (node (ref "UF1") (pin "6") (pinfunction "VS_6") (pintype "passive"))
    )
    (net (code "9") (name "/NOZZLE1_M2") (class "Default")
      (node (ref "CF9") (pin "1") (pintype "passive"))
      (node (ref "J4") (pin "2") (pinfunction "2_2") (pintype "passive"))
      (node (ref "RF14") (pin "2") (pintype "passive"))
      (node (ref "U3") (pin "1") (pinfunction "RS+_1") (pintype "passive"))
    )
    (net (code "10") (name "/Output") (class "Default")
      (node (ref "RF16") (pin "1") (pintype "passive"))
      (node (ref "RF2") (pin "1") (pintype "passive"))
      (node (ref "RF23") (pin "1") (pintype "passive"))
      (node (ref "RF24") (pin "1") (pintype "passive"))
      (node (ref "U3") (pin "5") (pinfunction "OUT_5") (pintype "passive"))
      (node (ref "UM1") (pin "52") (pinfunction "PTC6/ADC1_SE4/LPUART1_RX/CAN1_RX/FTM3_CH2_52") (pintype "passive"))
    )
    (net (code "11") (name "/PGND") (class "Default")
      (node (ref "C1") (pin "2") (pintype "passive"))
      (node (ref "C2") (pin "2") (pintype "passive"))
      (node (ref "CP10") (pin "2") (pintype "passive"))
      (node (ref "CP11") (pin "2") (pintype "passive"))
      (node (ref "CP12") (pin "2") (pintype "passive"))
      (node (ref "CP13") (pin "2") (pinfunction "2_2") (pintype "passive"))
      (node (ref "CP2") (pin "2") (pintype "passive"))
      (node (ref "CP3") (pin "2") (pintype "passive"))
      (node (ref "CP4") (pin "2") (pintype "passive"))
      (node (ref "CP5") (pin "2") (pintype "passive"))
      (node (ref "CP6") (pin "2") (pintype "passive"))
      (node (ref "CP7") (pin "2") (pintype "passive"))
      (node (ref "CP8") (pin "2") (pintype "passive"))
      (node (ref "DC1") (pin "3") (pinfunction "G_3") (pintype "passive"))
      (node (ref "J2") (pin "2") (pinfunction "2_2") (pintype "passive"))
      (node (ref "J3") (pin "2") (pinfunction "2_2") (pintype "passive"))
      (node (ref "LP3") (pin "1") (pintype "passive"))
      (node (ref "QF2") (pin "3") (pinfunction "S_3") (pintype "passive"))
      (node (ref "QF4") (pin "3") (pinfunction "S_3") (pintype "passive"))
      (node (ref "RP1") (pin "2") (pintype "passive"))
      (node (ref "RPB1") (pin "1") (pintype "passive"))
      (node (ref "UF1") (pin "4") (pinfunction "COM_4") (pintype "passive"))
      (node (ref "UF2") (pin "4") (pinfunction "COM_4") (pintype "passive"))
      (node (ref "UP1") (pin "0") (pinfunction "PAD_0") (pintype "passive"))
      (node (ref "UP1") (pin "10") (pinfunction "AGND_10") (pintype "passive"))
      (node (ref "UP1") (pin "15") (pinfunction "PGND_15") (pintype "passive"))
      (node (ref "UP1") (pin "16") (pinfunction "PGND_16") (pintype "passive"))
      (node (ref "UP1") (pin "6") (pinfunction "SYNC_6") (pintype "passive"))
      (node (ref "UP2") (pin "2") (pinfunction "GND_2") (pintype "passive"))
    )
    (net (code "12") (name "/PWR_5V") (class "Default")
      (node (ref "CP4") (pin "1") (pintype "passive"))
      (node (ref "CP6") (pin "1") (pintype "passive"))
      (node (ref "CP7") (pin "1") (pintype "passive"))
      (node (ref "CP8") (pin "1") (pintype "passive"))
      (node (ref "CPF1") (pin "1") (pintype "passive"))
      (node (ref "LP1") (pin "2") (pinfunction "2_2") (pintype "passive"))
      (node (ref "LP2") (pin "1") (pintype "passive"))
      (node (ref "RPT1") (pin "2") (pintype "passive"))
      (node (ref "UP1") (pin "5") (pinfunction "BIAS_5") (pintype "passive"))
    )
    (net (code "13") (name "/RESET") (class "Default")
      (node (ref "CM1") (pin "1") (pintype "passive"))
      (node (ref "JM1") (pin "6") (pinfunction "6_6") (pintype "passive"))
      (node (ref "RM3") (pin "1") (pintype "passive"))
      (node (ref "UM1") (pin "63") (pinfunction "PTA5/~{RESET}_63") (pintype "passive"))
    )
    (net (code "14") (name "/SWD_CLK") (class "Default")
      (node (ref "RM4") (pin "2") (pintype "passive"))
      (node (ref "UM1") (pin "62") (pinfunction "PTC4/JTAG_TCLK/SWD_CLK/FTM1_CH0_62") (pintype "passive"))
    )
    (net (code "15") (name "/SWD_DIO") (class "Default")
      (node (ref "RM5") (pin "2") (pintype "passive"))
      (node (ref "UM1") (pin "64") (pinfunction "PTA4/JTAG_TMS/SWD_DIO_64") (pintype "passive"))
    )
    (net (code "16") (name "/T1") (class "Default")
      (node (ref "U2") (pin "2") (pinfunction "2_2") (pintype "passive"))
      (node (ref "UM1") (pin "18") (pinfunction "PTB5/FTM0_CH5/LPSPI0_PCS1/LPSPI0_PCS0_18") (pintype "passive"))
    )
    (net (code "17") (name "/T1_H") (class "Default")
      (node (ref "P1") (pin "3") (pinfunction "3_3") (pintype "passive"))
      (node (ref "UM1") (pin "26") (pinfunction "PTC0/ADC0_SE8/FTM0_CH0/LPSPI2_SIN/FTM1_CH6_26") (pintype "passive"))
    )
    (net (code "18") (name "/T1_N") (class "Default")
      (node (ref "RF7") (pin "1") (pintype "passive"))
      (node (ref "UM1") (pin "25") (pinfunction "PTC1/ADC0_SE9/FTM0_CH1/LPSPI2_SOUT/FTM1_CH7_25") (pintype "passive"))
    )
    (net (code "19") (name "/T2") (class "Default")
      (node (ref "U2") (pin "5") (pinfunction "5_5") (pintype "passive"))
      (node (ref "UM1") (pin "19") (pinfunction "PTB4/FTM0_CH4/LPSPI0_SOUT_19") (pintype "passive"))
    )
    (net (code "20") (name "/T2_H") (class "Default")
      (node (ref "P2") (pin "3") (pinfunction "3_3") (pintype "passive"))
      (node (ref "UM1") (pin "20") (pinfunction "PTC3/ADC0_SE11/FTM0_CH3/CAN0_TX/LPUART0_TX_20") (pintype "passive"))
    )
    (net (code "21") (name "/T2_N") (class "Default")
      (node (ref "RF13") (pin "1") (pintype "passive"))
      (node (ref "UM1") (pin "21") (pinfunction "PTC2/ADC0_SE10/FTM0_CH2/CAN0_RX/LPUART0_RX_21") (pintype "passive"))
    )
    (net (code "22") (name "/VIinj1S-") (class "Default")
      (node (ref "CF6") (pin "2") (pinfunction "2_2") (pintype "passive"))
      (node (ref "CF9") (pin "2") (pintype "passive"))
      (node (ref "QF3") (pin "3") (pinfunction "S_3") (pintype "passive"))
      (node (ref "QF4") (pin "2") (pinfunction "D_2") (pintype "passive"))
      (node (ref "RF14") (pin "1") (pintype "passive"))
      (node (ref "U3") (pin "2") (pinfunction "RS-_2") (pintype "passive"))
      (node (ref "UF2") (pin "6") (pinfunction "VS_6") (pintype "passive"))
    )
    (net (code "23") (name "/XTAL") (class "Default")
      (node (ref "CM6") (pin "1") (pintype "passive"))
      (node (ref "RM6") (pin "1") (pintype "passive"))
      (node (ref "UM1") (pin "12") (pinfunction "PTB6/XTAL_12") (pintype "passive"))
      (node (ref "YM1") (pin "3") (pinfunction "3_3") (pintype "passive"))
    )
    (net (code "24") (name "2.5V") (class "Default")
      (node (ref "CS1") (pin "1") (pintype "passive"))
      (node (ref "RF20") (pin "2") (pintype "passive"))
      (node (ref "RS1") (pin "1") (pintype "passive"))
      (node (ref "RS2") (pin "2") (pintype "passive"))
      (node (ref "U3") (pin "7") (pinfunction "REFIN_7") (pintype "passive"))
    )
    (net (code "25") (name "GND") (class "Default")
      (node (ref "CC1") (pin "2") (pintype "passive"))
      (node (ref "CC2") (pin "2") (pintype "passive"))
      (node (ref "CC3") (pin "2") (pintype "passive"))
      (node (ref "CF1") (pin "1") (pintype "passive"))
      (node (ref "CF2") (pin "2") (pintype "passive"))
      (node (ref "CF4") (pin "1") (pintype "passive"))
      (node (ref "CF5") (pin "1") (pintype "passive"))
      (node (ref "CF7") (pin "2") (pintype "passive"))
      (node (ref "CF8") (pin "2") (pintype "passive"))
      (node (ref "CM1") (pin "2") (pintype "passive"))
      (node (ref "CM2") (pin "2") (pintype "passive"))
      (node (ref "CM3") (pin "2") (pintype "passive"))
      (node (ref "CM4") (pin "2") (pintype "passive"))
      (node (ref "CM5") (pin "2") (pintype "passive"))
      (node (ref "CM6") (pin "2") (pintype "passive"))
      (node (ref "CP9") (pin "2") (pintype "passive"))
      (node (ref "CS1") (pin "2") (pintype "passive"))
      (node (ref "JM1") (pin "2") (pinfunction "2_2") (pintype "passive"))
      (node (ref "JM1") (pin "3") (pinfunction "3_3") (pintype "passive"))
      (node (ref "LP3") (pin "2") (pintype "passive"))
      (node (ref "RC1") (pin "2") (pintype "passive"))
      (node (ref "RF22") (pin "1") (pintype "passive"))
      (node (ref "RF9") (pin "1") (pintype "passive"))
      (node (ref "RM1") (pin "2") (pintype "passive"))
      (node (ref "RS2") (pin "1") (pintype "passive"))
      (node (ref "U1") (pin "4") (pinfunction "4_4") (pintype "passive"))
      (node (ref "U2") (pin "7") (pinfunction "7_7") (pintype "passive"))
      (node (ref "U3") (pin "3") (pinfunction "SHDN_3") (pintype "passive"))
      (node (ref "U3") (pin "4") (pinfunction "GND_4") (pintype "passive"))
      (node (ref "UC1") (pin "2") (pinfunction "GND_2") (pintype "passive"))
      (node (ref "UM1") (pin "10") (pinfunction "VSS1_10") (pintype "passive"))
      (node (ref "UM1") (pin "40") (pinfunction "VSS2_40") (pintype "passive"))
      (node (ref "YM1") (pin "2") (pinfunction "2_2") (pintype "passive"))
      (node (ref "YM1") (pin "4") (pinfunction "4_4") (pintype "passive"))
    )
    (net (code "26") (name "Net-(CC3-Pad1)") (class "Default")
      (node (ref "CC3") (pin "1") (pintype "passive"))
      (node (ref "RC2") (pin "1") (pintype "passive"))
      (node (ref "RC3") (pin "1") (pintype "passive"))
    )
    (net (code "27") (name "Net-(CP1-Pad2)") (class "Default")
      (node (ref "CP1") (pin "2") (pintype "passive"))
      (node (ref "LP1") (pin "1") (pinfunction "1_1") (pintype "passive"))
      (node (ref "UP1") (pin "1") (pinfunction "SW_1") (pintype "passive"))
      (node (ref "UP1") (pin "2") (pinfunction "SW_2") (pintype "passive"))
    )
    (net (code "28") (name "Net-(JM1-Pad4)") (class "Default")
      (node (ref "JM1") (pin "4") (pinfunction "4_4") (pintype "passive"))
      (node (ref "RM1") (pin "1") (pintype "passive"))
      (node (ref "RM4") (pin "1") (pintype "passive"))
    )
    (net (code "29") (name "Net-(JM1-Pad5)") (class "Default")
      (node (ref "JM1") (pin "5") (pinfunction "5_5") (pintype "passive"))
      (node (ref "RM2") (pin "1") (pintype "passive"))
      (node (ref "RM5") (pin "1") (pintype "passive"))
    )
    (net (code "30") (name "Net-(P1-Pad1)") (class "Default")
      (node (ref "P1") (pin "1") (pinfunction "1_1") (pintype "passive"))
      (node (ref "RF3") (pin "1") (pintype "passive"))
    )
    (net (code "31") (name "Net-(P1-Pad2)") (class "Default")
      (node (ref "P1") (pin "2") (pinfunction "2_2") (pintype "passive"))
      (node (ref "U2") (pin "3") (pinfunction "3_3") (pintype "passive"))
    )
    (net (code "32") (name "Net-(P2-Pad1)") (class "Default")
      (node (ref "P2") (pin "1") (pinfunction "1_1") (pintype "passive"))
      (node (ref "RF11") (pin "1") (pintype "passive"))
    )
    (net (code "33") (name "Net-(P2-Pad2)") (class "Default")
      (node (ref "P2") (pin "2") (pinfunction "2_2") (pintype "passive"))
      (node (ref "U2") (pin "6") (pinfunction "6_6") (pintype "passive"))
    )
    (net (code "34") (name "Net-(QF1-Pad1)") (class "Default")
      (node (ref "QF1") (pin "1") (pinfunction "1_1") (pintype "passive"))
      (node (ref "RF5") (pin "2") (pintype "passive"))
    )
    (net (code "35") (name "Net-(QF2-Pad1)") (class "Default")
      (node (ref "QF2") (pin "1") (pinfunction "1_1") (pintype "passive"))
      (node (ref "RF8") (pin "2") (pintype "passive"))
    )
    (net (code "36") (name "Net-(QF3-Pad1)") (class "Default")
      (node (ref "QF3") (pin "1") (pinfunction "1_1") (pintype "passive"))
      (node (ref "RF12") (pin "2") (pintype "passive"))
    )
    (net (code "37") (name "Net-(QF4-Pad1)") (class "Default")
      (node (ref "QF4") (pin "1") (pinfunction "1_1") (pintype "passive"))
      (node (ref "RF17") (pin "2") (pintype "passive"))
    )
    (net (code "38") (name "Net-(RF1-Pad2)") (class "Default")
      (node (ref "RF1") (pin "2") (pintype "passive"))
      (node (ref "RF10") (pin "2") (pintype "passive"))
      (node (ref "U1") (pin "1") (pinfunction "1_1") (pintype "passive"))
      (node (ref "U2") (pin "1") (pinfunction "1_1") (pintype "passive"))
    )
    (net (code "39") (name "Net-(RF4-Pad1)") (class "Default")
      (node (ref "RF4") (pin "1") (pintype "passive"))
      (node (ref "RF6") (pin "1") (pintype "passive"))
      (node (ref "RF9") (pin "2") (pintype "passive"))
    )
    (net (code "40") (name "Net-(RF15-Pad1)") (class "Default")
      (node (ref "RF15") (pin "1") (pintype "passive"))
      (node (ref "RF21") (pin "2") (pintype "passive"))
      (node (ref "U1") (pin "7") (pinfunction "7_7") (pintype "passive"))
      (node (ref "U2") (pin "4") (pinfunction "4_4") (pintype "passive"))
    )
    (net (code "41") (name "Net-(RF18-Pad1)") (class "Default")
      (node (ref "RF18") (pin "1") (pintype "passive"))
      (node (ref "RF19") (pin "1") (pintype "passive"))
      (node (ref "RF22") (pin "2") (pintype "passive"))
    )
    (net (code "42") (name "Net-(U1A-+)") (class "Default")
      (node (ref "RF10") (pin "1") (pintype "passive"))
      (node (ref "RF6") (pin "2") (pintype "passive"))
      (node (ref "U1") (pin "3") (pinfunction "+_3") (pintype "passive"))
    )
    (net (code "43") (name "Net-(U1A--)") (class "Default")
      (node (ref "RF2") (pin "2") (pintype "passive"))
      (node (ref "U1") (pin "2") (pinfunction "-_2") (pintype "passive"))
    )
    (net (code "44") (name "Net-(U1B-+)") (class "Default")
      (node (ref "RF19") (pin "2") (pintype "passive"))
      (node (ref "RF21") (pin "1") (pintype "passive"))
      (node (ref "U1") (pin "5") (pinfunction "+_5") (pintype "passive"))
    )
    (net (code "45") (name "Net-(U1B--)") (class "Default")
      (node (ref "RF16") (pin "2") (pintype "passive"))
      (node (ref "U1") (pin "6") (pinfunction "-_6") (pintype "passive"))
    )
    (net (code "46") (name "Net-(U3-FB)") (class "Default")
      (node (ref "RF20") (pin "1") (pintype "passive"))
      (node (ref "RF23") (pin "2") (pintype "passive"))
      (node (ref "U3") (pin "6") (pinfunction "FB_6") (pintype "passive"))
    )
    (net (code "47") (name "Net-(UC1-CANH)") (class "Default")
      (node (ref "LC1") (pin "1") (pinfunction "1_1") (pintype "passive"))
      (node (ref "UC1") (pin "7") (pinfunction "CANH_7") (pintype "passive"))
    )
    (net (code "48") (name "Net-(UC1-CANL)") (class "Default")
      (node (ref "LC1") (pin "2") (pinfunction "2_2") (pintype "passive"))
      (node (ref "UC1") (pin "6") (pinfunction "CANL_6") (pintype "passive"))
    )
    (net (code "49") (name "Net-(UC1-STB)") (class "Default")
      (node (ref "RC1") (pin "1") (pintype "passive"))
      (node (ref "UC1") (pin "8") (pinfunction "STB_8") (pintype "passive"))
    )
    (net (code "50") (name "Net-(UF1-HIN)") (class "Default")
      (node (ref "RF3") (pin "2") (pintype "passive"))
      (node (ref "UF1") (pin "2") (pinfunction "HIN_2") (pintype "passive"))
    )
    (net (code "51") (name "Net-(UF1-HO)") (class "Default")
      (node (ref "RF5") (pin "1") (pintype "passive"))
      (node (ref "UF1") (pin "7") (pinfunction "HO_7") (pintype "passive"))
    )
    (net (code "52") (name "Net-(UF1-LO)") (class "Default")
      (node (ref "RF8") (pin "1") (pintype "passive"))
      (node (ref "UF1") (pin "5") (pinfunction "LO_5") (pintype "passive"))
    )
    (net (code "53") (name "Net-(UF1-VB)") (class "Default")
      (node (ref "CF3") (pin "1") (pinfunction "1_1") (pintype "passive"))
      (node (ref "DF1") (pin "2") (pinfunction "2_2") (pintype "passive"))
      (node (ref "UF1") (pin "8") (pinfunction "VB_8") (pintype "passive"))
    )
    (net (code "54") (name "Net-(UF1-~{LIN})") (class "Default")
      (node (ref "RF7") (pin "2") (pintype "passive"))
      (node (ref "UF1") (pin "3") (pinfunction "~{LIN}_3") (pintype "passive"))
    )
    (net (code "55") (name "Net-(UF2-HIN)") (class "Default")
      (node (ref "RF11") (pin "2") (pintype "passive"))
      (node (ref "UF2") (pin "2") (pinfunction "HIN_2") (pintype "passive"))
    )
    (net (code "56") (name "Net-(UF2-HO)") (class "Default")
      (node (ref "RF12") (pin "1") (pintype "passive"))
      (node (ref "UF2") (pin "7") (pinfunction "HO_7") (pintype "passive"))
    )
    (net (code "57") (name "Net-(UF2-LO)") (class "Default")
      (node (ref "RF17") (pin "1") (pintype "passive"))
      (node (ref "UF2") (pin "5") (pinfunction "LO_5") (pintype "passive"))
    )
    (net (code "58") (name "Net-(UF2-VB)") (class "Default")
      (node (ref "CF6") (pin "1") (pinfunction "1_1") (pintype "passive"))
      (node (ref "DF2") (pin "2") (pinfunction "2_2") (pintype "passive"))
      (node (ref "UF2") (pin "8") (pinfunction "VB_8") (pintype "passive"))
    )
    (net (code "59") (name "Net-(UF2-~{LIN})") (class "Default")
      (node (ref "RF13") (pin "2") (pintype "passive"))
      (node (ref "UF2") (pin "3") (pinfunction "~{LIN}_3") (pintype "passive"))
    )
    (net (code "60") (name "Net-(UP1-CBOOT)") (class "Default")
      (node (ref "CP1") (pin "1") (pintype "passive"))
      (node (ref "UP1") (pin "3") (pinfunction "CBOOT_3") (pintype "passive"))
    )
    (net (code "61") (name "Net-(UP1-FB)") (class "Default")
      (node (ref "CPF1") (pin "2") (pintype "passive"))
      (node (ref "RPB1") (pin "2") (pintype "passive"))
      (node (ref "RPT1") (pin "1") (pintype "passive"))
      (node (ref "UP1") (pin "9") (pinfunction "FB_9") (pintype "passive"))
    )
    (net (code "62") (name "Net-(UP1-RT)") (class "Default")
      (node (ref "RP1") (pin "1") (pintype "passive"))
      (node (ref "UP1") (pin "7") (pinfunction "RT_7") (pintype "passive"))
    )
    (net (code "63") (name "Net-(UP1-VCC)") (class "Default")
      (node (ref "CP5") (pin "1") (pintype "passive"))
      (node (ref "UP1") (pin "4") (pinfunction "VCC_4") (pintype "passive"))
    )
    (net (code "64") (name "Net-(UP2-IN)") (class "Default")
      (node (ref "CP12") (pin "1") (pintype "passive"))
      (node (ref "DP1") (pin "2") (pinfunction "2_2") (pintype "passive"))
      (node (ref "UP2") (pin "3") (pinfunction "IN_3") (pintype "passive"))
    )
    (net (code "65") (name "VBAT") (class "Default")
      (node (ref "C1") (pin "1") (pintype "passive"))
      (node (ref "C2") (pin "1") (pintype "passive"))
      (node (ref "J2") (pin "1") (pinfunction "1_1") (pintype "passive"))
      (node (ref "QF1") (pin "2") (pinfunction "D_2") (pintype "passive"))
      (node (ref "QF3") (pin "2") (pinfunction "D_2") (pintype "passive"))
    )
    (net (code "66") (name "VCC") (class "Default")
      (node (ref "CC1") (pin "1") (pintype "passive"))
      (node (ref "CC2") (pin "1") (pintype "passive"))
      (node (ref "CF1") (pin "2") (pintype "passive"))
      (node (ref "CF2") (pin "1") (pintype "passive"))
      (node (ref "CF4") (pin "2") (pintype "passive"))
      (node (ref "CF5") (pin "2") (pintype "passive"))
      (node (ref "CF7") (pin "1") (pintype "passive"))
      (node (ref "CF8") (pin "1") (pintype "passive"))
      (node (ref "CM2") (pin "1") (pintype "passive"))
      (node (ref "CM3") (pin "1") (pintype "passive"))
      (node (ref "CM4") (pin "1") (pintype "passive"))
      (node (ref "CP9") (pin "1") (pintype "passive"))
      (node (ref "JM1") (pin "1") (pinfunction "1_1") (pintype "passive"))
      (node (ref "LP2") (pin "2") (pintype "passive"))
      (node (ref "RF1") (pin "1") (pintype "passive"))
      (node (ref "RF15") (pin "2") (pintype "passive"))
      (node (ref "RF18") (pin "2") (pintype "passive"))
      (node (ref "RF24") (pin "2") (pintype "passive"))
      (node (ref "RF4") (pin "2") (pintype "passive"))
      (node (ref "RM2") (pin "2") (pintype "passive"))
      (node (ref "RM3") (pin "2") (pintype "passive"))
      (node (ref "RS1") (pin "2") (pintype "passive"))
      (node (ref "U1") (pin "8") (pinfunction "8_8") (pintype "passive"))
      (node (ref "U2") (pin "14") (pinfunction "14_14") (pintype "passive"))
      (node (ref "U3") (pin "8") (pinfunction "VCC_8") (pintype "passive"))
      (node (ref "UC1") (pin "3") (pinfunction "Vcc_3") (pintype "passive"))
      (node (ref "UC1") (pin "5") (pinfunction "Vio_5") (pintype "passive"))
      (node (ref "UM1") (pin "41") (pinfunction "VDD2_41") (pintype "passive"))
      (node (ref "UM1") (pin "7") (pinfunction "VDD1_7") (pintype "passive"))
      (node (ref "UM1") (pin "8") (pinfunction "VDDA_8") (pintype "passive"))
      (node (ref "UM1") (pin "9") (pinfunction "VREFH_9") (pintype "passive"))
    )
    (net (code "67") (name "unconnected-(P1-Pad4)") (class "Default")
      (node (ref "P1") (pin "4") (pinfunction "4_4") (pintype "passive"))
    )
    (net (code "68") (name "unconnected-(P2-Pad4)") (class "Default")
      (node (ref "P2") (pin "4") (pinfunction "4_4") (pintype "passive"))
    )
    (net (code "69") (name "unconnected-(U1-Pad8)") (class "Default")
      (node (ref "U1") (pin "8") (pinfunction "8_8") (pintype "passive"))
    )
    (net (code "70") (name "unconnected-(UM1-PTA0{slash}ADC0_SE0{slash}FTM2_CH1{slash}LPUART0_CTS-Pad50)") (class "Default")
      (node (ref "UM1") (pin "50") (pinfunction "PTA0/ADC0_SE0/FTM2_CH1/LPUART0_CTS_50") (pintype "passive+no_connect"))
    )
    (net (code "71") (name "unconnected-(UM1-PTA1{slash}ADC0_SE1{slash}FTM1_CH1{slash}LPUART0_RTS-Pad49)") (class "Default")
      (node (ref "UM1") (pin "49") (pinfunction "PTA1/ADC0_SE1/FTM1_CH1/LPUART0_RTS_49") (pintype "passive+no_connect"))
    )
    (net (code "72") (name "unconnected-(UM1-PTA2{slash}ADC1_SE0{slash}FTM3_CH0{slash}LPUART0_RX-Pad48)") (class "Default")
      (node (ref "UM1") (pin "48") (pinfunction "PTA2/ADC1_SE0/FTM3_CH0/LPUART0_RX_48") (pintype "passive+no_connect"))
    )
    (net (code "73") (name "unconnected-(UM1-PTA3{slash}ADC1_SE1{slash}FTM3_CH1{slash}LPUART0_TX-Pad47)") (class "Default")
      (node (ref "UM1") (pin "47") (pinfunction "PTA3/ADC1_SE1/FTM3_CH1/LPUART0_TX_47") (pintype "passive+no_connect"))
    )
    (net (code "74") (name "unconnected-(UM1-PTA6{slash}ADC0_SE2{slash}LPSPI1_PCS1{slash}LPUART1_CTS-Pad38)") (class "Default")
      (node (ref "UM1") (pin "38") (pinfunction "PTA6/ADC0_SE2/LPSPI1_PCS1/LPUART1_CTS_38") (pintype "passive+no_connect"))
    )
    (net (code "75") (name "unconnected-(UM1-PTA7{slash}ADC0_SE3{slash}LPUART1_RTS-Pad37)") (class "Default")
      (node (ref "UM1") (pin "37") (pinfunction "PTA7/ADC0_SE3/LPUART1_RTS_37") (pintype "passive+no_connect"))
    )
    (net (code "76") (name "unconnected-(UM1-PTA10{slash}JTAG_TDO{slash}FTM1_CH4-Pad58)") (class "Default")
      (node (ref "UM1") (pin "58") (pinfunction "PTA10/JTAG_TDO/FTM1_CH4_58") (pintype "passive+no_connect"))
    )
    (net (code "77") (name "unconnected-(UM1-PTA11{slash}FTM1_CH5-Pad57)") (class "Default")
      (node (ref "UM1") (pin "57") (pinfunction "PTA11/FTM1_CH5_57") (pintype "passive+no_connect"))
    )
    (net (code "78") (name "unconnected-(UM1-PTB0{slash}ADC0_SE4{slash}ADC1_SE14{slash}LPUART0_RX{slash}LPSPI0_PCS0{slash}CAN0_RX-Pad34)") (class "Default")
      (node (ref "UM1") (pin "34") (pinfunction "PTB0/ADC0_SE4/ADC1_SE14/LPUART0_RX/LPSPI0_PCS0/CAN0_RX_34") (pintype "passive+no_connect"))
    )
    (net (code "79") (name "unconnected-(UM1-PTB1{slash}ADC0_SE5{slash}ADC1_SE15{slash}LPUART0_TX{slash}CAN0_TX-Pad33)") (class "Default")
      (node (ref "UM1") (pin "33") (pinfunction "PTB1/ADC0_SE5/ADC1_SE15/LPUART0_TX/CAN0_TX_33") (pintype "passive+no_connect"))
    )
    (net (code "80") (name "unconnected-(UM1-PTB2{slash}ADC0_SE6{slash}FTM1_CH0{slash}LPSPI0_SCK-Pad32)") (class "Default")
      (node (ref "UM1") (pin "32") (pinfunction "PTB2/ADC0_SE6/FTM1_CH0/LPSPI0_SCK_32") (pintype "passive+no_connect"))
    )
    (net (code "81") (name "unconnected-(UM1-PTB3{slash}ADC0_SE7{slash}FTM1_CH1{slash}LPSPI0_SIN-Pad31)") (class "Default")
      (node (ref "UM1") (pin "31") (pinfunction "PTB3/ADC0_SE7/FTM1_CH1/LPSPI0_SIN_31") (pintype "passive+no_connect"))
    )
    (net (code "82") (name "unconnected-(UM1-PTB12{slash}ADC1_SE7{slash}FTM0_CH0{slash}CAN2_RX-Pad43)") (class "Default")
      (node (ref "UM1") (pin "43") (pinfunction "PTB12/ADC1_SE7/FTM0_CH0/CAN2_RX_43") (pintype "passive+no_connect"))
    )
    (net (code "83") (name "unconnected-(UM1-PTB13{slash}ADC1_SE8{slash}ADC0_SE8{slash}FTM0_CH1{slash}CAN2_TX-Pad42)") (class "Default")
      (node (ref "UM1") (pin "42") (pinfunction "PTB13/ADC1_SE8/ADC0_SE8/FTM0_CH1/CAN2_TX_42") (pintype "passive+no_connect"))
    )
    (net (code "84") (name "unconnected-(UM1-PTC5{slash}JTAG_TDI{slash}FTM2_CH0-Pad61)") (class "Default")
      (node (ref "UM1") (pin "61") (pinfunction "PTC5/JTAG_TDI/FTM2_CH0_61") (pintype "passive+no_connect"))
    )
    (net (code "85") (name "unconnected-(UM1-PTC7{slash}ADC1_SE5{slash}LPUART1_TX{slash}CAN1_TX{slash}FTM3_CH3-Pad51)") (class "Default")
      (node (ref "UM1") (pin "51") (pinfunction "PTC7/ADC1_SE5/LPUART1_TX/CAN1_TX/FTM3_CH3_51") (pintype "passive+no_connect"))
    )
    (net (code "86") (name "unconnected-(UM1-PTC8{slash}LPUART1_RX-Pad36)") (class "Default")
      (node (ref "UM1") (pin "36") (pinfunction "PTC8/LPUART1_RX_36") (pintype "passive+no_connect"))
    )
    (net (code "87") (name "unconnected-(UM1-PTC9{slash}LPUART1_TX-Pad35)") (class "Default")
      (node (ref "UM1") (pin "35") (pinfunction "PTC9/LPUART1_TX_35") (pintype "passive+no_connect"))
    )
    (net (code "88") (name "unconnected-(UM1-PTC14{slash}ADC0_SE12{slash}FTM1_CH2{slash}LPSPI2_PCS0-Pad30)") (class "Default")
      (node (ref "UM1") (pin "30") (pinfunction "PTC14/ADC0_SE12/FTM1_CH2/LPSPI2_PCS0_30") (pintype "passive"))
    )
    (net (code "89") (name "unconnected-(UM1-PTC15{slash}ADC0_SE13{slash}FTM1_CH3{slash}LPSPI2_SCK-Pad29)") (class "Default")
      (node (ref "UM1") (pin "29") (pinfunction "PTC15/ADC0_SE13/FTM1_CH3/LPSPI2_SCK_29") (pintype "passive"))
    )
    (net (code "90") (name "unconnected-(UM1-PTC16{slash}ADC0_SE14{slash}CAN2_RX-Pad28)") (class "Default")
      (node (ref "UM1") (pin "28") (pinfunction "PTC16/ADC0_SE14/CAN2_RX_28") (pintype "passive+no_connect"))
    )
    (net (code "91") (name "unconnected-(UM1-PTC17{slash}ADC0_SE15{slash}CAN2_TX-Pad27)") (class "Default")
      (node (ref "UM1") (pin "27") (pinfunction "PTC17/ADC0_SE15/CAN2_TX_27") (pintype "passive+no_connect"))
    )
    (net (code "92") (name "unconnected-(UM1-PTD0{slash}FTM0_CH2{slash}LPSPI1_SCK{slash}FTM2_CH0-Pad2)") (class "Default")
      (node (ref "UM1") (pin "2") (pinfunction "PTD0/FTM0_CH2/LPSPI1_SCK/FTM2_CH0_2") (pintype "passive+no_connect"))
    )
    (net (code "93") (name "unconnected-(UM1-PTD1{slash}FTM0_CH3{slash}LPSPI1_SIN{slash}FTM2_CH1-Pad1)") (class "Default")
      (node (ref "UM1") (pin "1") (pinfunction "PTD1/FTM0_CH3/LPSPI1_SIN/FTM2_CH1_1") (pintype "passive+no_connect"))
    )
    (net (code "94") (name "unconnected-(UM1-PTD2{slash}ADC1_SE2{slash}FTM3_CH4{slash}LPSPI1_SOUT-Pad46)") (class "Default")
      (node (ref "UM1") (pin "46") (pinfunction "PTD2/ADC1_SE2/FTM3_CH4/LPSPI1_SOUT_46") (pintype "passive+no_connect"))
    )
    (net (code "95") (name "unconnected-(UM1-PTD3{slash}ADC1_SE3{slash}FTM3_CH5{slash}LPSPI1_PCS0-Pad45)") (class "Default")
      (node (ref "UM1") (pin "45") (pinfunction "PTD3/ADC1_SE3/FTM3_CH5/LPSPI1_PCS0_45") (pintype "passive+no_connect"))
    )
    (net (code "96") (name "unconnected-(UM1-PTD4{slash}ADC1_SE6-Pad44)") (class "Default")
      (node (ref "UM1") (pin "44") (pinfunction "PTD4/ADC1_SE6_44") (pintype "passive+no_connect"))
    )
    (net (code "97") (name "unconnected-(UM1-PTD5{slash}FTM2_CH3-Pad24)") (class "Default")
      (node (ref "UM1") (pin "24") (pinfunction "PTD5/FTM2_CH3_24") (pintype "passive+no_connect"))
    )
    (net (code "98") (name "unconnected-(UM1-PTD6{slash}LPUART2_RX-Pad23)") (class "Default")
      (node (ref "UM1") (pin "23") (pinfunction "PTD6/LPUART2_RX_23") (pintype "passive+no_connect"))
    )
    (net (code "99") (name "unconnected-(UM1-PTD7{slash}LPUART2_TX-Pad22)") (class "Default")
      (node (ref "UM1") (pin "22") (pinfunction "PTD7/LPUART2_TX_22") (pintype "passive+no_connect"))
    )
    (net (code "100") (name "unconnected-(UM1-PTD15{slash}FTM0_CH0{slash}LPSPI0_SCK-Pad15)") (class "Default")
      (node (ref "UM1") (pin "15") (pinfunction "PTD15/FTM0_CH0/LPSPI0_SCK_15") (pintype "passive+no_connect"))
    )
    (net (code "101") (name "unconnected-(UM1-PTD16{slash}FTM0_CH1{slash}LPSPI0_SIN-Pad14)") (class "Default")
      (node (ref "UM1") (pin "14") (pinfunction "PTD16/FTM0_CH1/LPSPI0_SIN_14") (pintype "passive+no_connect"))
    )
    (net (code "102") (name "unconnected-(UM1-PTE0{slash}LPSPI0_SCK{slash}LPSPI1_SOUT-Pad60)") (class "Default")
      (node (ref "UM1") (pin "60") (pinfunction "PTE0/LPSPI0_SCK/LPSPI1_SOUT_60") (pintype "passive+no_connect"))
    )
    (net (code "103") (name "unconnected-(UM1-PTE1{slash}LPSPI0_SIN{slash}LPSPI1_PCS0-Pad59)") (class "Default")
      (node (ref "UM1") (pin "59") (pinfunction "PTE1/LPSPI0_SIN/LPSPI1_PCS0_59") (pintype "passive+no_connect"))
    )
    (net (code "104") (name "unconnected-(UM1-PTE2{slash}ADC1_SE10{slash}LPSPI0_SOUT{slash}FTM3_CH6-Pad54)") (class "Default")
      (node (ref "UM1") (pin "54") (pinfunction "PTE2/ADC1_SE10/LPSPI0_SOUT/FTM3_CH6_54") (pintype "passive+no_connect"))
    )
    (net (code "105") (name "unconnected-(UM1-PTE3-Pad13)") (class "Default")
      (node (ref "UM1") (pin "13") (pinfunction "PTE3_13") (pintype "passive+no_connect"))
    )
    (net (code "106") (name "unconnected-(UM1-PTE4{slash}FTM2_CH2{slash}CAN0_RX-Pad6)") (class "Default")
      (node (ref "UM1") (pin "6") (pinfunction "PTE4/FTM2_CH2/CAN0_RX_6") (pintype "passive+no_connect"))
    )
    (net (code "107") (name "unconnected-(UM1-PTE5{slash}FTM2_CH3{slash}CAN0_TX-Pad5)") (class "Default")
      (node (ref "UM1") (pin "5") (pinfunction "PTE5/FTM2_CH3/CAN0_TX_5") (pintype "passive+no_connect"))
    )
    (net (code "108") (name "unconnected-(UM1-PTE6{slash}ADC1_SE11{slash}LPSPI0_PCS2{slash}FTM3_CH7-Pad53)") (class "Default")
      (node (ref "UM1") (pin "53") (pinfunction "PTE6/ADC1_SE11/LPSPI0_PCS2/FTM3_CH7_53") (pintype "passive+no_connect"))
    )
    (net (code "109") (name "unconnected-(UM1-PTE7{slash}FTM0_CH7-Pad39)") (class "Default")
      (node (ref "UM1") (pin "39") (pinfunction "PTE7/FTM0_CH7_39") (pintype "passive+no_connect"))
    )
    (net (code "110") (name "unconnected-(UM1-PTE8{slash}FTM0_CH6-Pad17)") (class "Default")
      (node (ref "UM1") (pin "17") (pinfunction "PTE8/FTM0_CH6_17") (pintype "passive+no_connect"))
    )
    (net (code "111") (name "unconnected-(UM1-PTE9{slash}FTM0_CH7-Pad16)") (class "Default")
      (node (ref "UM1") (pin "16") (pinfunction "PTE9/FTM0_CH7_16") (pintype "passive+no_connect"))
    )
    (net (code "112") (name "unconnected-(UM1-PTE10{slash}LPSPI2_PCS1{slash}FTM2_CH4-Pad4)") (class "Default")
      (node (ref "UM1") (pin "4") (pinfunction "PTE10/LPSPI2_PCS1/FTM2_CH4_4") (pintype "passive+no_connect"))
    )
    (net (code "113") (name "unconnected-(UM1-PTE11{slash}LPSPI2_PCS0{slash}FTM2_CH5-Pad3)") (class "Default")
      (node (ref "UM1") (pin "3") (pinfunction "PTE11/LPSPI2_PCS0/FTM2_CH5_3") (pintype "passive+no_connect"))
    )
    (net (code "114") (name "unconnected-(UP1-PGOOD-Pad8)") (class "Default")
      (node (ref "UP1") (pin "8") (pinfunction "PGOOD_8") (pintype "passive+no_connect"))
    )
    (net (code "115") (name "unconnected-(UP1-SS-Pad11)") (class "Default")
      (node (ref "UP1") (pin "11") (pinfunction "SS_11") (pintype "passive+no_connect"))
    )
  )
)
